# Power_system.net
KiCad netlist of a schematic drawn in Altium Designer
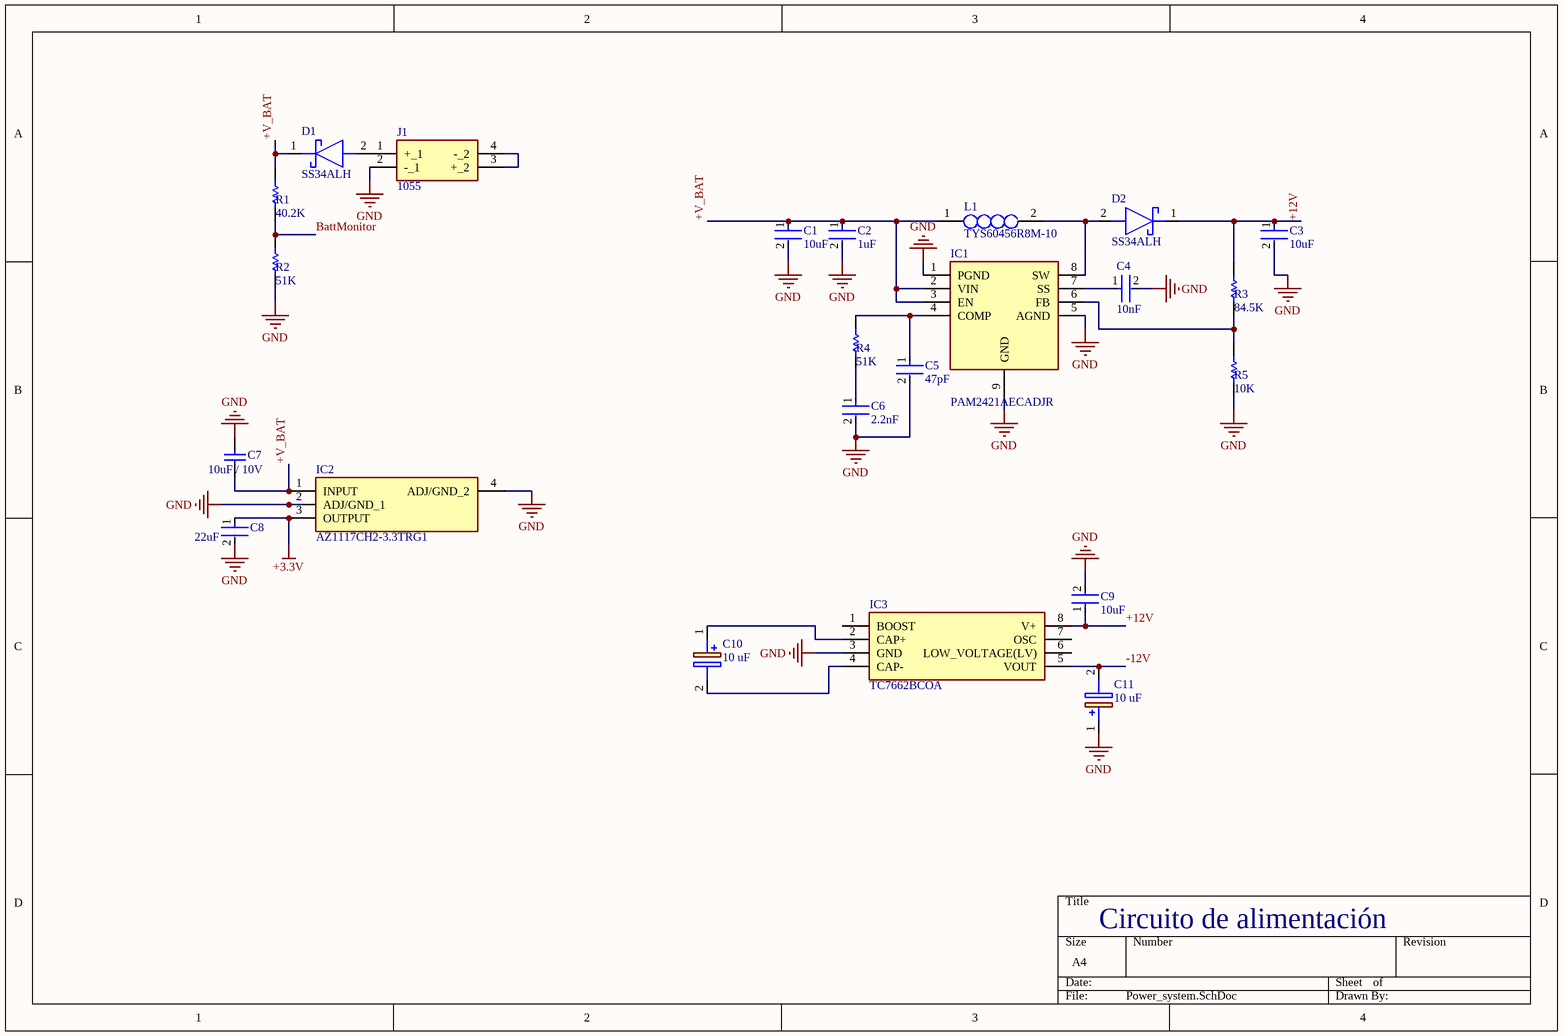
[diagram p0: Power_system.SchDoc]

(export (version "E")
  (design (tool "Eeschema 10.0.6"))
  (components
    (comp (ref "C1")
      (value "10uF")
      (footprint "FP-GRM188-0_2-MFG")
      (description "Chip Multilayer Ceramic Capacitors for General Purpose, 0603, 22uF, X5R, 15%, 20%, 4V")
      (fields (field (name "VOLTAGE") "4V") (field (name "TOLERANCE") "20%"))
      (libsource (lib "Altium Content Vault") (part "11868f565c42a9108669ba33697ecf6"))
    )
    (comp (ref "C2")
      (value "1uF")
      (footprint "FP-GRM188-0_2-MFG")
      (description "Chip Multilayer Ceramic Capacitors for General Purpose, 0603, 22uF, X5R, 15%, 20%, 4V")
      (fields (field (name "VOLTAGE") "4V") (field (name "TOLERANCE") "20%"))
      (libsource (lib "Altium Content Vault") (part "11868f565c42a9108669ba33697ecf6"))
    )
    (comp (ref "C3")
      (value "10uF")
      (footprint "FP-GRM188-0_2-MFG")
      (description "Chip Multilayer Ceramic Capacitors for General Purpose, 0603, 22uF, X5R, 15%, 20%, 4V")
      (fields (field (name "VOLTAGE") "4V") (field (name "TOLERANCE") "20%"))
      (libsource (lib "Altium Content Vault") (part "11868f565c42a9108669ba33697ecf6"))
    )
    (comp (ref "C4")
      (value "10nF")
      (footprint "FP-GRM188-0_2-MFG")
      (description "Chip Multilayer Ceramic Capacitors for General Purpose, 0603, 22uF, X5R, 15%, 20%, 4V")
      (fields (field (name "VOLTAGE") "4V") (field (name "TOLERANCE") "20%"))
      (libsource (lib "Altium Content Vault") (part "11868f565c42a9108669ba33697ecf6"))
    )
    (comp (ref "C5")
      (value "47pF")
      (footprint "FP-GRM188-0_2-MFG")
      (description "Chip Multilayer Ceramic Capacitors for General Purpose, 0603, 22uF, X5R, 15%, 20%, 4V")
      (fields (field (name "VOLTAGE") "4V") (field (name "TOLERANCE") "20%"))
      (libsource (lib "Altium Content Vault") (part "11868f565c42a9108669ba33697ecf6"))
    )
    (comp (ref "C6")
      (value "2.2nF")
      (footprint "FP-GRM188-0_2-MFG")
      (description "Chip Multilayer Ceramic Capacitors for General Purpose, 0603, 22uF, X5R, 15%, 20%, 4V")
      (fields (field (name "VOLTAGE") "4V") (field (name "TOLERANCE") "20%"))
      (libsource (lib "Altium Content Vault") (part "11868f565c42a9108669ba33697ecf6"))
    )
    (comp (ref "C7")
      (value "10uF / 10V")
      (footprint "CAPC1608X90X35LL15T15")
      (fields (field (name "PART NUMBER") "C0603C105K9PACTU") (field (name "MANUFACTURER") "Kemet"))
      (libsource (lib "Altium Content Vault") (part "CAP"))
    )
    (comp (ref "C8")
      (value "22uF")
      (footprint "FP-GRM188-0_2-MFG")
      (description "Chip Multilayer Ceramic Capacitors for General Purpose, 0603, 22uF, X5R, 15%, 20%, 4V")
      (fields (field (name "VOLTAGE") "4V") (field (name "TOLERANCE") "20%"))
      (libsource (lib "Altium Content Vault") (part "11868f565c42a9108669ba33697ecf6"))
    )
    (comp (ref "C9")
      (value "10uF")
      (footprint "FP-GRM188-0_2-MFG")
      (description "Chip Multilayer Ceramic Capacitors for General Purpose, 0603, 22uF, X5R, 15%, 20%, 4V")
      (fields (field (name "VOLTAGE") "4V") (field (name "TOLERANCE") "20%"))
      (libsource (lib "Altium Content Vault") (part "11868f565c42a9108669ba33697ecf6"))
    )
    (comp (ref "C10")
      (value "10 uF")
      (footprint "SamacSys:CAPAE430X550N")
      (description "Capacitor Polarised")
      (fields
        (field (name "MANUFACTURER_PART_NUMBER") "865080340001")
        (field (name "MOUSER PART NUMBER") "710-865080340001")
      )
      (libsource (lib "") (part "865080340001_1"))
    )
    (comp (ref "C11")
      (value "10 uF")
      (footprint "SamacSys:CAPAE430X550N")
      (description "Capacitor Polarised")
      (fields
        (field (name "MANUFACTURER_PART_NUMBER") "865080340001")
        (field (name "MOUSER PART NUMBER") "710-865080340001")
      )
      (libsource (lib "*") (part "865080340001"))
    )
    (comp (ref "D1")
      (value "SS34ALH")
      (footprint "SamacSys:SODFL5226X100N")
      (description "Schottky Diode")
      (fields (field (name "MOUSER PART NUMBER") "821-SS34ALH"))
      (libsource (lib "*") (part "SS34ALH"))
    )
    (comp (ref "D2")
      (value "SS34ALH")
      (footprint "SamacSys:SODFL5226X100N")
      (description "Schottky Diode")
      (fields (field (name "MOUSER PART NUMBER") "821-SS34ALH"))
      (libsource (lib "*") (part "SS34ALH"))
    )
    (comp (ref "IC1")
      (value "PAM2421AECADJR")
      (footprint "SamacSys:SOIC127P600X150-9N")
      (description "Integrated Circuit")
      (fields (field (name "MOUSER PART NUMBER") "621-PAM2421AECADJR"))
      (libsource (lib "*") (part "PAM2421AECADJR"))
    )
    (comp (ref "IC2")
      (value "AZ1117CH2-3.3TRG1")
      (footprint "SamacSys:SOT230P700X180-4N")
      (description "Integrated Circuit")
      (fields (field (name "MOUSER PART NUMBER") "621-AZ1117CH2-33TRG1"))
      (libsource (lib "*") (part "AZ1117CH2-3.3TRG1"))
    )
    (comp (ref "IC3")
      (value "TC7662BCOA")
      (footprint "SamacSys:SOIC127P600X175-8N")
      (description "Integrated Circuit")
      (fields (field (name "MOUSER PART NUMBER") "579-TC7662BCOA"))
      (libsource (lib "*") (part "TC7662BCOA"))
    )
    (comp (ref "J1")
      (value "1055")
      (footprint "SamacSys:1055")
      (description "Connector")
      (fields (field (name "MOUSER PART NUMBER") "534-1055"))
      (libsource (lib "*") (part "1055"))
    )
    (comp (ref "L1")
      (value "TYS60456R8M-10")
      (footprint "SamacSys:INDPM6060X470N")
      (description "Inductor")
      (fields (field (name "MOUSER PART NUMBER") "875-TYS60456R8M-10"))
      (libsource (lib "*") (part "TYS60456R8M-10"))
    )
    (comp (ref "R1")
      (value "40.2K")
      (footprint "RESC1608X55X30ML20T20")
      (fields (field (name "PART NUMBER") "ERA3AEB333V") (field (name "MANUFACTURER") "Panasonic"))
      (libsource (lib "Altium Content Vault") (part "RES"))
    )
    (comp (ref "R2")
      (value "51K")
      (footprint "RESC1608X55X30ML20T20")
      (fields (field (name "PART NUMBER") "ERA3AEB333V") (field (name "MANUFACTURER") "Panasonic"))
      (libsource (lib "Altium Content Vault") (part "RES"))
    )
    (comp (ref "R3")
      (value "84.5K")
      (footprint "RESC1608X55X30ML20T20")
      (fields (field (name "PART NUMBER") "ERA3AEB333V") (field (name "MANUFACTURER") "Panasonic"))
      (libsource (lib "Altium Content Vault") (part "RES"))
    )
    (comp (ref "R4")
      (value "51K")
      (footprint "RESC1608X55X30ML20T20")
      (fields (field (name "PART NUMBER") "ERA3AEB333V") (field (name "MANUFACTURER") "Panasonic"))
      (libsource (lib "Altium Content Vault") (part "RES"))
    )
    (comp (ref "R5")
      (value "10K")
      (footprint "RESC1608X55X30ML20T20")
      (fields (field (name "PART NUMBER") "ERA3AEB333V") (field (name "MANUFACTURER") "Panasonic"))
      (libsource (lib "Altium Content Vault") (part "RES"))
    )
  )
  (nets
    (net (code "1") (name "+3.3V") (class "Default")
      (node (ref "C8") (pin "1") (pinfunction "1_1") (pintype "passive"))
      (node (ref "IC2") (pin "3") (pinfunction "OUTPUT_3") (pintype "passive"))
    )
    (net (code "2") (name "/+12V") (class "Default")
      (node (ref "C3") (pin "1") (pinfunction "1_1") (pintype "passive"))
      (node (ref "C9") (pin "1") (pinfunction "1_1") (pintype "passive"))
      (node (ref "D2") (pin "1") (pinfunction "K_1") (pintype "passive"))
      (node (ref "IC3") (pin "8") (pinfunction "V+_8") (pintype "passive"))
      (node (ref "R3") (pin "2") (pinfunction "2_2") (pintype "passive"))
    )
    (net (code "3") (name "/+V_BAT") (class "Default")
      (node (ref "C1") (pin "1") (pinfunction "1_1") (pintype "passive"))
      (node (ref "C2") (pin "1") (pinfunction "1_1") (pintype "passive"))
      (node (ref "C7") (pin "2") (pinfunction "2_2") (pintype "passive"))
      (node (ref "D1") (pin "1") (pinfunction "K_1") (pintype "passive"))
      (node (ref "IC1") (pin "2") (pinfunction "VIN_2") (pintype "passive"))
      (node (ref "IC1") (pin "3") (pinfunction "EN_3") (pintype "passive"))
      (node (ref "IC2") (pin "1") (pinfunction "INPUT_1") (pintype "passive"))
      (node (ref "L1") (pin "1") (pinfunction "1_1") (pintype "passive"))
      (node (ref "R1") (pin "2") (pinfunction "2_2") (pintype "passive"))
    )
    (net (code "4") (name "/-12V") (class "Default")
      (node (ref "C11") (pin "2") (pinfunction "-_2") (pintype "passive"))
      (node (ref "IC3") (pin "5") (pinfunction "VOUT_5") (pintype "passive"))
    )
    (net (code "5") (name "/BattMonitor") (class "Default")
      (node (ref "R1") (pin "1") (pinfunction "1_1") (pintype "passive"))
      (node (ref "R2") (pin "2") (pinfunction "2_2") (pintype "passive"))
    )
    (net (code "6") (name "GND") (class "Default")
      (node (ref "C1") (pin "2") (pinfunction "2_2") (pintype "passive"))
      (node (ref "C11") (pin "1") (pinfunction "+_1") (pintype "passive"))
      (node (ref "C2") (pin "2") (pinfunction "2_2") (pintype "passive"))
      (node (ref "C3") (pin "2") (pinfunction "2_2") (pintype "passive"))
      (node (ref "C4") (pin "2") (pinfunction "2_2") (pintype "passive"))
      (node (ref "C5") (pin "2") (pinfunction "2_2") (pintype "passive"))
      (node (ref "C6") (pin "2") (pinfunction "2_2") (pintype "passive"))
      (node (ref "C7") (pin "1") (pinfunction "1_1") (pintype "passive"))
      (node (ref "C8") (pin "2") (pinfunction "2_2") (pintype "passive"))
      (node (ref "C9") (pin "2") (pinfunction "2_2") (pintype "passive"))
      (node (ref "IC1") (pin "1") (pinfunction "PGND_1") (pintype "passive"))
      (node (ref "IC1") (pin "5") (pinfunction "AGND_5") (pintype "passive"))
      (node (ref "IC1") (pin "9") (pinfunction "GND_9") (pintype "passive"))
      (node (ref "IC2") (pin "2") (pinfunction "ADJ/GND_1_2") (pintype "passive"))
      (node (ref "IC2") (pin "4") (pinfunction "ADJ/GND_2_4") (pintype "passive"))
      (node (ref "IC3") (pin "3") (pinfunction "GND_3") (pintype "passive"))
      (node (ref "J1") (pin "2") (pinfunction "-_1_2") (pintype "passive"))
      (node (ref "R2") (pin "1") (pinfunction "1_1") (pintype "passive"))
      (node (ref "R5") (pin "1") (pinfunction "1_1") (pintype "passive"))
    )
    (net (code "7") (name "Net-(C6-Pad1)") (class "Default")
      (node (ref "C6") (pin "1") (pinfunction "1_1") (pintype "passive"))
      (node (ref "R4") (pin "1") (pinfunction "1_1") (pintype "passive"))
    )
    (net (code "8") (name "Net-(C10-+)") (class "Default")
      (node (ref "C10") (pin "1") (pinfunction "+_1") (pintype "passive"))
      (node (ref "IC3") (pin "2") (pinfunction "CAP+_2") (pintype "passive"))
    )
    (net (code "9") (name "Net-(C10--)") (class "Default")
      (node (ref "C10") (pin "2") (pinfunction "-_2") (pintype "passive"))
      (node (ref "IC3") (pin "4") (pinfunction "CAP-_4") (pintype "passive"))
    )
    (net (code "10") (name "Net-(D1-A)") (class "Default")
      (node (ref "D1") (pin "2") (pinfunction "A_2") (pintype "passive"))
      (node (ref "J1") (pin "1") (pinfunction "+_1_1") (pintype "passive"))
    )
    (net (code "11") (name "Net-(D2-A)") (class "Default")
      (node (ref "D2") (pin "2") (pinfunction "A_2") (pintype "passive"))
      (node (ref "IC1") (pin "8") (pinfunction "SW_8") (pintype "passive"))
      (node (ref "L1") (pin "2") (pinfunction "2_2") (pintype "passive"))
    )
    (net (code "12") (name "Net-(IC1-COMP)") (class "Default")
      (node (ref "C5") (pin "1") (pinfunction "1_1") (pintype "passive"))
      (node (ref "IC1") (pin "4") (pinfunction "COMP_4") (pintype "passive"))
      (node (ref "R4") (pin "2") (pinfunction "2_2") (pintype "passive"))
    )
    (net (code "13") (name "Net-(IC1-FB)") (class "Default")
      (node (ref "IC1") (pin "6") (pinfunction "FB_6") (pintype "passive"))
      (node (ref "R3") (pin "1") (pinfunction "1_1") (pintype "passive"))
      (node (ref "R5") (pin "2") (pinfunction "2_2") (pintype "passive"))
    )
    (net (code "14") (name "Net-(IC1-SS)") (class "Default")
      (node (ref "C4") (pin "1") (pinfunction "1_1") (pintype "passive"))
      (node (ref "IC1") (pin "7") (pinfunction "SS_7") (pintype "passive"))
    )
    (net (code "15") (name "Net-(J1-+_2)") (class "Default")
      (node (ref "J1") (pin "3") (pinfunction "+_2_3") (pintype "passive"))
      (node (ref "J1") (pin "4") (pinfunction "-_2_4") (pintype "passive"))
    )
    (net (code "16") (name "unconnected-(IC3-BOOST-Pad1)") (class "Default")
      (node (ref "IC3") (pin "1") (pinfunction "BOOST_1") (pintype "passive"))
    )
    (net (code "17") (name "unconnected-(IC3-LOW_VOLTAGE(LV)-Pad6)") (class "Default")
      (node (ref "IC3") (pin "6") (pinfunction "LOW_VOLTAGE(LV)_6") (pintype "passive"))
    )
    (net (code "18") (name "unconnected-(IC3-OSC-Pad7)") (class "Default")
      (node (ref "IC3") (pin "7") (pinfunction "OSC_7") (pintype "passive"))
    )
  )
)
